# Controller.net
KiCad netlist of a schematic drawn in EasyEDA
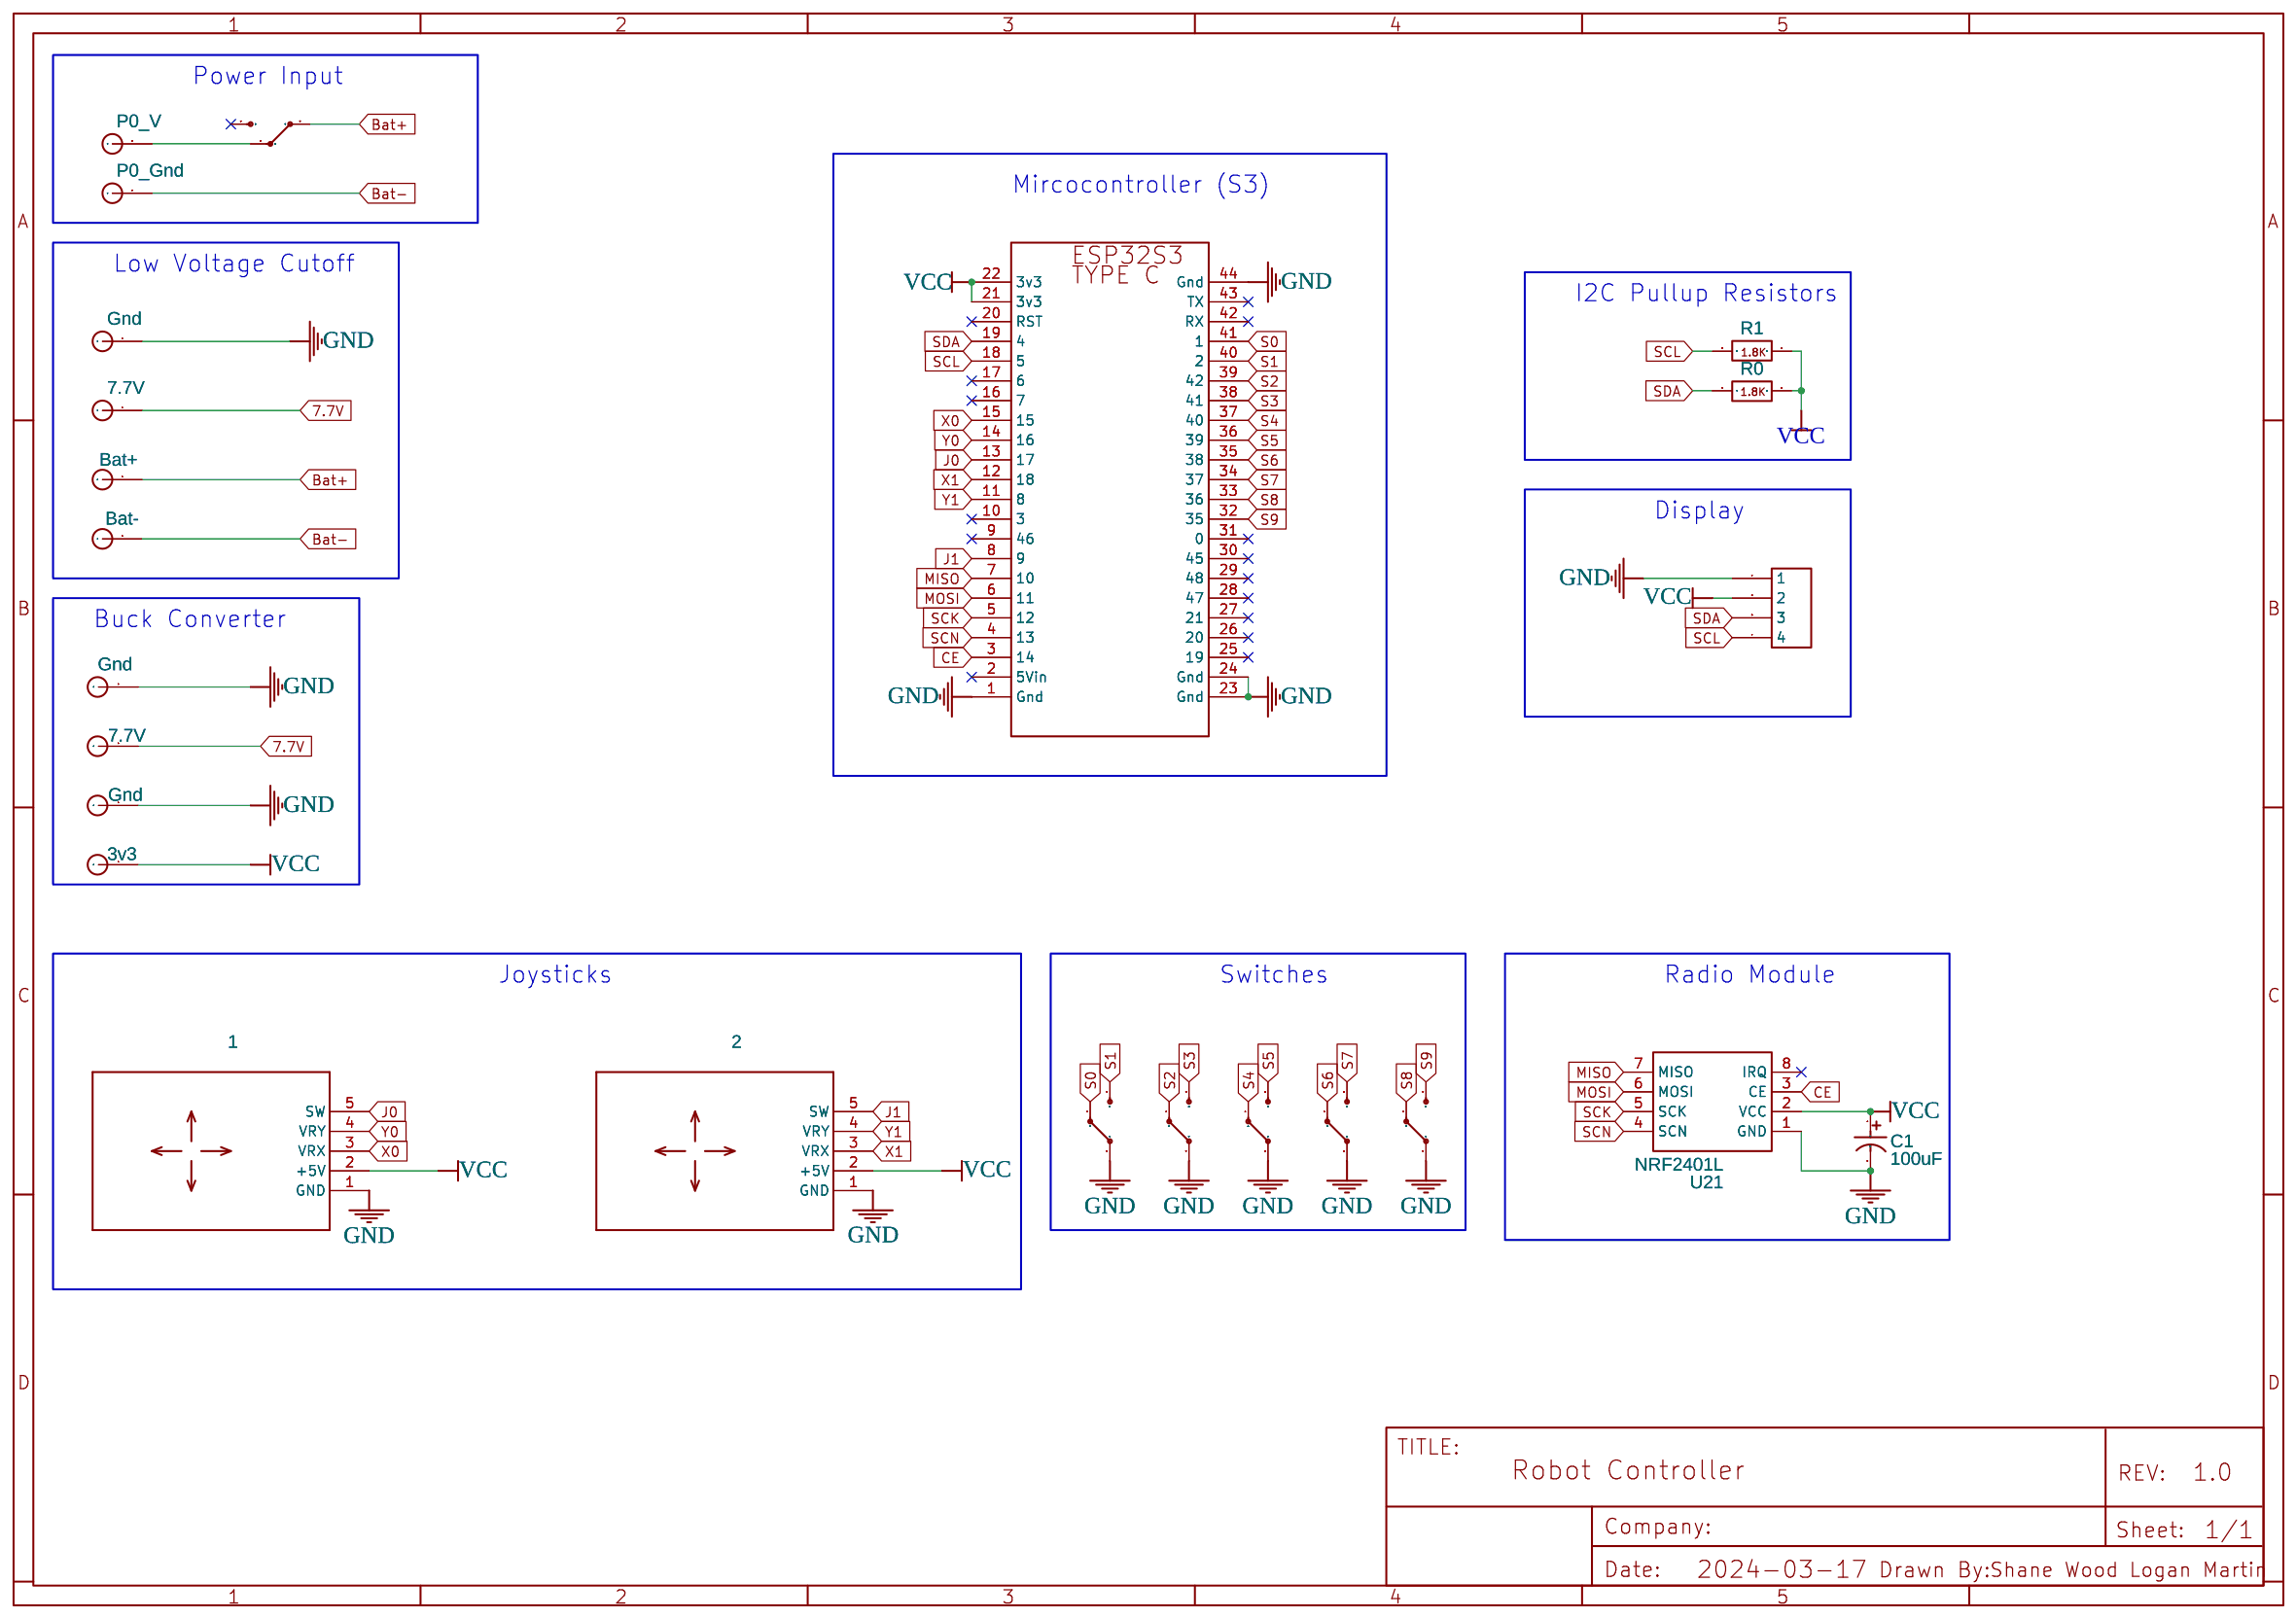
[diagram p0: schematic sheet]

(export (version "E")
  (design (tool "Eeschema 10.0.6"))
  (components
    (comp (ref "1") (value "JOYSTICK-2AXIS-BUTTON") (libsource (lib "") (part "JOYSTICK-2AXIS-BUTTON")))
    (comp (ref "2") (value "JOYSTICK-2AXIS-BUTTON") (libsource (lib "") (part "JOYSTICK-2AXIS-BUTTON")))
    (comp (ref "C1")
      (value "100uF")
      (fields (field (name "Manufacturer Part") "Jweo"))
      (libsource (lib "") (part "CAP-POL-1"))
    )
    (comp (ref "R1") (value "R1") (libsource (lib "") (part "1.8K_R_1/2W_1")))
    (comp (ref "R2") (value "R0") (libsource (lib "") (part "1.8K_R_1/2W")))
    (comp (ref "U1") (value "NO") (libsource (lib "") (part "TOGGLESWITCH SPST_SWITCH-SPDT COPY_1")))
    (comp (ref "U2")
      (value "P0_V")
      (fields (field (name "Manufacturer Part") "Wire Hole"))
      (libsource (lib "") (part "Wire Hole 14AWG_1"))
    )
    (comp (ref "U3")
      (value "P0_Gnd")
      (fields (field (name "Manufacturer Part") "Wire Hole"))
      (libsource (lib "") (part "Wire Hole 14AWG_1"))
    )
    (comp (ref "U4")
      (value "Bat+")
      (fields (field (name "Manufacturer Part") "Wire Hole"))
      (libsource (lib "") (part "Wire Hole 14AWG_1"))
    )
    (comp (ref "U5")
      (value "Gnd")
      (fields (field (name "Manufacturer Part") "Wire Hole"))
      (libsource (lib "") (part "Wire Hole 14AWG_1"))
    )
    (comp (ref "U6")
      (value "Bat-")
      (fields (field (name "Manufacturer Part") "Wire Hole"))
      (libsource (lib "") (part "Wire Hole 14AWG_1"))
    )
    (comp (ref "U7")
      (value "7.7V")
      (fields (field (name "Manufacturer Part") "Wire Hole"))
      (libsource (lib "") (part "Wire Hole 14AWG_1"))
    )
    (comp (ref "U8")
      (value "NO")
      (fields
        (field (name "Manufacturer Part") "Female header pitch2.54mm")
        (field (name "Manufacturer") "ReliaPro")
      )
      (libsource (lib "") (part "Header-Female-2.54_1x4"))
    )
    (comp (ref "U9") (value "ESP32S3 TypeC") (libsource (lib "") (part "ESP32S3 TypeC")))
    (comp (ref "U11")
      (value "Gnd")
      (fields (field (name "Manufacturer Part") "Wire Hole"))
      (libsource (lib "") (part "Wire Hole 14AWG"))
    )
    (comp (ref "U12")
      (value "Gnd")
      (fields (field (name "Manufacturer Part") "Wire Hole"))
      (libsource (lib "") (part "Wire Hole 14AWG"))
    )
    (comp (ref "U14")
      (value "7.7V")
      (fields (field (name "Manufacturer Part") "Wire Hole"))
      (libsource (lib "") (part "Wire Hole 14AWG"))
    )
    (comp (ref "U15")
      (value "3v3")
      (fields (field (name "Manufacturer Part") "Wire Hole"))
      (libsource (lib "") (part "Wire Hole 14AWG"))
    )
    (comp (ref "U16") (value "NO") (libsource (lib "") (part "TOGGLESWITCH SPST_SWITCH-SPDT COPY")))
    (comp (ref "U17") (value "NO") (libsource (lib "") (part "TOGGLESWITCH SPST_SWITCH-SPDT COPY")))
    (comp (ref "U18") (value "NO") (libsource (lib "") (part "TOGGLESWITCH SPST_SWITCH-SPDT COPY")))
    (comp (ref "U19") (value "NO") (libsource (lib "") (part "TOGGLESWITCH SPST_SWITCH-SPDT COPY")))
    (comp (ref "U20") (value "NO") (libsource (lib "") (part "TOGGLESWITCH SPST_SWITCH-SPDT COPY")))
    (comp (ref "U21")
      (value "NRF2401L")
      (fields (field (name "Manufacturer Part") "nrf2401l"))
      (libsource (lib "") (part "NRF2401L"))
    )
  )
  (nets
    (net (code "1") (name "7.7V") (class "Default")
      (node (ref "U14") (pin "1") (pinfunction "1_1") (pintype "unspecified"))
      (node (ref "U7") (pin "1") (pinfunction "1_1") (pintype "unspecified"))
    )
    (net (code "2") (name "Bat+") (class "Default")
      (node (ref "U1") (pin "2") (pinfunction "P_2") (pintype "unspecified"))
      (node (ref "U4") (pin "1") (pinfunction "1_1") (pintype "unspecified"))
    )
    (net (code "3") (name "Bat-") (class "Default")
      (node (ref "U3") (pin "1") (pinfunction "1_1") (pintype "unspecified"))
      (node (ref "U6") (pin "1") (pinfunction "1_1") (pintype "unspecified"))
    )
    (net (code "4") (name "CE") (class "Default")
      (node (ref "U21") (pin "3") (pinfunction "CE_3") (pintype "unspecified"))
      (node (ref "U9") (pin "3") (pinfunction "14_3") (pintype "unspecified"))
    )
    (net (code "5") (name "GND") (class "Default")
      (node (ref "1") (pin "1") (pinfunction "GND_1") (pintype "bidirectional"))
      (node (ref "2") (pin "1") (pinfunction "GND_1") (pintype "bidirectional"))
      (node (ref "C1") (pin "2") (pinfunction "2_2") (pintype "input"))
      (node (ref "U11") (pin "1") (pinfunction "1_1") (pintype "unspecified"))
      (node (ref "U12") (pin "1") (pinfunction "1_1") (pintype "unspecified"))
      (node (ref "U16") (pin "2") (pinfunction "P_2") (pintype "unspecified"))
      (node (ref "U17") (pin "2") (pinfunction "P_2") (pintype "unspecified"))
      (node (ref "U18") (pin "2") (pinfunction "P_2") (pintype "unspecified"))
      (node (ref "U19") (pin "2") (pinfunction "P_2") (pintype "unspecified"))
      (node (ref "U20") (pin "2") (pinfunction "P_2") (pintype "unspecified"))
      (node (ref "U21") (pin "1") (pinfunction "GND_1") (pintype "unspecified"))
      (node (ref "U5") (pin "1") (pinfunction "1_1") (pintype "unspecified"))
      (node (ref "U8") (pin "1") (pinfunction "1_1") (pintype "input"))
      (node (ref "U9") (pin "1") (pinfunction "Gnd_1") (pintype "unspecified"))
      (node (ref "U9") (pin "23") (pinfunction "Gnd_23") (pintype "unspecified"))
      (node (ref "U9") (pin "24") (pinfunction "Gnd_24") (pintype "unspecified"))
      (node (ref "U9") (pin "44") (pinfunction "Gnd_44") (pintype "unspecified"))
    )
    (net (code "6") (name "J0") (class "Default")
      (node (ref "1") (pin "5") (pinfunction "SW_5") (pintype "bidirectional"))
      (node (ref "U9") (pin "13") (pinfunction "17_13") (pintype "unspecified"))
    )
    (net (code "7") (name "J1") (class "Default")
      (node (ref "2") (pin "5") (pinfunction "SW_5") (pintype "bidirectional"))
      (node (ref "U9") (pin "8") (pinfunction "9_8") (pintype "unspecified"))
    )
    (net (code "8") (name "MISO") (class "Default")
      (node (ref "U21") (pin "7") (pinfunction "MISO_7") (pintype "unspecified"))
      (node (ref "U9") (pin "7") (pinfunction "10_7") (pintype "unspecified"))
    )
    (net (code "9") (name "MOSI") (class "Default")
      (node (ref "U21") (pin "6") (pinfunction "MOSI_6") (pintype "unspecified"))
      (node (ref "U9") (pin "6") (pinfunction "11_6") (pintype "unspecified"))
    )
    (net (code "10") (name "Net-(U1-O)") (class "Default")
      (node (ref "U1") (pin "1") (pinfunction "O_1") (pintype "unspecified"))
      (node (ref "U2") (pin "1") (pinfunction "1_1") (pintype "unspecified"))
    )
    (net (code "11") (name "S0") (class "Default")
      (node (ref "U16") (pin "1") (pinfunction "O_1") (pintype "unspecified"))
      (node (ref "U9") (pin "41") (pinfunction "1_41") (pintype "unspecified"))
    )
    (net (code "12") (name "S1") (class "Default")
      (node (ref "U16") (pin "3") (pinfunction "S_3") (pintype "unspecified"))
      (node (ref "U9") (pin "40") (pinfunction "2_40") (pintype "unspecified"))
    )
    (net (code "13") (name "S2") (class "Default")
      (node (ref "U17") (pin "1") (pinfunction "O_1") (pintype "unspecified"))
      (node (ref "U9") (pin "39") (pinfunction "42_39") (pintype "unspecified"))
    )
    (net (code "14") (name "S3") (class "Default")
      (node (ref "U17") (pin "3") (pinfunction "S_3") (pintype "unspecified"))
      (node (ref "U9") (pin "38") (pinfunction "41_38") (pintype "unspecified"))
    )
    (net (code "15") (name "S4") (class "Default")
      (node (ref "U18") (pin "1") (pinfunction "O_1") (pintype "unspecified"))
      (node (ref "U9") (pin "37") (pinfunction "40_37") (pintype "unspecified"))
    )
    (net (code "16") (name "S5") (class "Default")
      (node (ref "U18") (pin "3") (pinfunction "S_3") (pintype "unspecified"))
      (node (ref "U9") (pin "36") (pinfunction "39_36") (pintype "unspecified"))
    )
    (net (code "17") (name "S6") (class "Default")
      (node (ref "U19") (pin "1") (pinfunction "O_1") (pintype "unspecified"))
      (node (ref "U9") (pin "35") (pinfunction "38_35") (pintype "unspecified"))
    )
    (net (code "18") (name "S7") (class "Default")
      (node (ref "U19") (pin "3") (pinfunction "S_3") (pintype "unspecified"))
      (node (ref "U9") (pin "34") (pinfunction "37_34") (pintype "unspecified"))
    )
    (net (code "19") (name "S8") (class "Default")
      (node (ref "U20") (pin "1") (pinfunction "O_1") (pintype "unspecified"))
      (node (ref "U9") (pin "33") (pinfunction "36_33") (pintype "unspecified"))
    )
    (net (code "20") (name "S9") (class "Default")
      (node (ref "U20") (pin "3") (pinfunction "S_3") (pintype "unspecified"))
      (node (ref "U9") (pin "32") (pinfunction "35_32") (pintype "unspecified"))
    )
    (net (code "21") (name "SCK") (class "Default")
      (node (ref "U21") (pin "5") (pinfunction "SCK_5") (pintype "unspecified"))
      (node (ref "U9") (pin "5") (pinfunction "12_5") (pintype "unspecified"))
    )
    (net (code "22") (name "SCL") (class "Default")
      (node (ref "R1") (pin "2") (pinfunction "2_2") (pintype "unspecified"))
      (node (ref "U8") (pin "4") (pinfunction "4_4") (pintype "input"))
      (node (ref "U9") (pin "18") (pinfunction "5_18") (pintype "unspecified"))
    )
    (net (code "23") (name "SCN") (class "Default")
      (node (ref "U21") (pin "4") (pinfunction "SCN_4") (pintype "unspecified"))
      (node (ref "U9") (pin "4") (pinfunction "13_4") (pintype "unspecified"))
    )
    (net (code "24") (name "SDA") (class "Default")
      (node (ref "R2") (pin "1") (pinfunction "1_1") (pintype "unspecified"))
      (node (ref "U8") (pin "3") (pinfunction "3_3") (pintype "input"))
      (node (ref "U9") (pin "19") (pinfunction "4_19") (pintype "unspecified"))
    )
    (net (code "25") (name "VCC") (class "Default")
      (node (ref "1") (pin "2") (pinfunction "+5V_2") (pintype "bidirectional"))
      (node (ref "2") (pin "2") (pinfunction "+5V_2") (pintype "bidirectional"))
      (node (ref "C1") (pin "1") (pinfunction "1_1") (pintype "input"))
      (node (ref "R1") (pin "1") (pinfunction "1_1") (pintype "unspecified"))
      (node (ref "R2") (pin "2") (pinfunction "2_2") (pintype "unspecified"))
      (node (ref "U15") (pin "1") (pinfunction "1_1") (pintype "unspecified"))
      (node (ref "U21") (pin "2") (pinfunction "VCC_2") (pintype "unspecified"))
      (node (ref "U8") (pin "2") (pinfunction "2_2") (pintype "input"))
      (node (ref "U9") (pin "21") (pinfunction "3v3_21") (pintype "unspecified"))
      (node (ref "U9") (pin "22") (pinfunction "3v3_22") (pintype "unspecified"))
    )
    (net (code "26") (name "X0") (class "Default")
      (node (ref "1") (pin "3") (pinfunction "VRX_3") (pintype "bidirectional"))
      (node (ref "U9") (pin "15") (pinfunction "15_15") (pintype "unspecified"))
    )
    (net (code "27") (name "X1") (class "Default")
      (node (ref "2") (pin "3") (pinfunction "VRX_3") (pintype "bidirectional"))
      (node (ref "U9") (pin "12") (pinfunction "18_12") (pintype "unspecified"))
    )
    (net (code "28") (name "Y0") (class "Default")
      (node (ref "1") (pin "4") (pinfunction "VRY_4") (pintype "bidirectional"))
      (node (ref "U9") (pin "14") (pinfunction "16_14") (pintype "unspecified"))
    )
    (net (code "29") (name "Y1") (class "Default")
      (node (ref "2") (pin "4") (pinfunction "VRY_4") (pintype "bidirectional"))
      (node (ref "U9") (pin "11") (pinfunction "8_11") (pintype "unspecified"))
    )
    (net (code "30") (name "unconnected-(U1-S-Pad3)") (class "Default")
      (node (ref "U1") (pin "3") (pinfunction "S_3") (pintype "unspecified+no_connect"))
    )
    (net (code "31") (name "unconnected-(U9-0-Pad31)") (class "Default")
      (node (ref "U9") (pin "31") (pinfunction "0_31") (pintype "unspecified+no_connect"))
    )
    (net (code "32") (name "unconnected-(U9-3-Pad10)") (class "Default")
      (node (ref "U9") (pin "10") (pinfunction "3_10") (pintype "unspecified+no_connect"))
    )
    (net (code "33") (name "unconnected-(U9-5Vin-Pad2)") (class "Default")
      (node (ref "U9") (pin "2") (pinfunction "5Vin_2") (pintype "unspecified+no_connect"))
    )
    (net (code "34") (name "unconnected-(U9-6-Pad17)") (class "Default")
      (node (ref "U9") (pin "17") (pinfunction "6_17") (pintype "unspecified+no_connect"))
    )
    (net (code "35") (name "unconnected-(U9-7-Pad16)") (class "Default")
      (node (ref "U9") (pin "16") (pinfunction "7_16") (pintype "unspecified+no_connect"))
    )
    (net (code "36") (name "unconnected-(U9-19-Pad25)") (class "Default")
      (node (ref "U9") (pin "25") (pinfunction "19_25") (pintype "unspecified+no_connect"))
    )
    (net (code "37") (name "unconnected-(U9-20-Pad26)") (class "Default")
      (node (ref "U9") (pin "26") (pinfunction "20_26") (pintype "unspecified+no_connect"))
    )
    (net (code "38") (name "unconnected-(U9-21-Pad27)") (class "Default")
      (node (ref "U9") (pin "27") (pinfunction "21_27") (pintype "unspecified+no_connect"))
    )
    (net (code "39") (name "unconnected-(U9-45-Pad30)") (class "Default")
      (node (ref "U9") (pin "30") (pinfunction "45_30") (pintype "unspecified+no_connect"))
    )
    (net (code "40") (name "unconnected-(U9-46-Pad9)") (class "Default")
      (node (ref "U9") (pin "9") (pinfunction "46_9") (pintype "unspecified+no_connect"))
    )
    (net (code "41") (name "unconnected-(U9-47-Pad28)") (class "Default")
      (node (ref "U9") (pin "28") (pinfunction "47_28") (pintype "unspecified+no_connect"))
    )
    (net (code "42") (name "unconnected-(U9-48-Pad29)") (class "Default")
      (node (ref "U9") (pin "29") (pinfunction "48_29") (pintype "unspecified+no_connect"))
    )
    (net (code "43") (name "unconnected-(U9-RST-Pad20)") (class "Default")
      (node (ref "U9") (pin "20") (pinfunction "RST_20") (pintype "unspecified+no_connect"))
    )
    (net (code "44") (name "unconnected-(U9-RX-Pad42)") (class "Default")
      (node (ref "U9") (pin "42") (pinfunction "RX_42") (pintype "unspecified+no_connect"))
    )
    (net (code "45") (name "unconnected-(U9-TX-Pad43)") (class "Default")
      (node (ref "U9") (pin "43") (pinfunction "TX_43") (pintype "unspecified+no_connect"))
    )
    (net (code "46") (name "unconnected-(U21-IRQ-Pad8)") (class "Default")
      (node (ref "U21") (pin "8") (pinfunction "IRQ_8") (pintype "unspecified+no_connect"))
    )
  )
)
